# Ring_3_C.net
KiCad netlist of a schematic drawn in Altium Designer
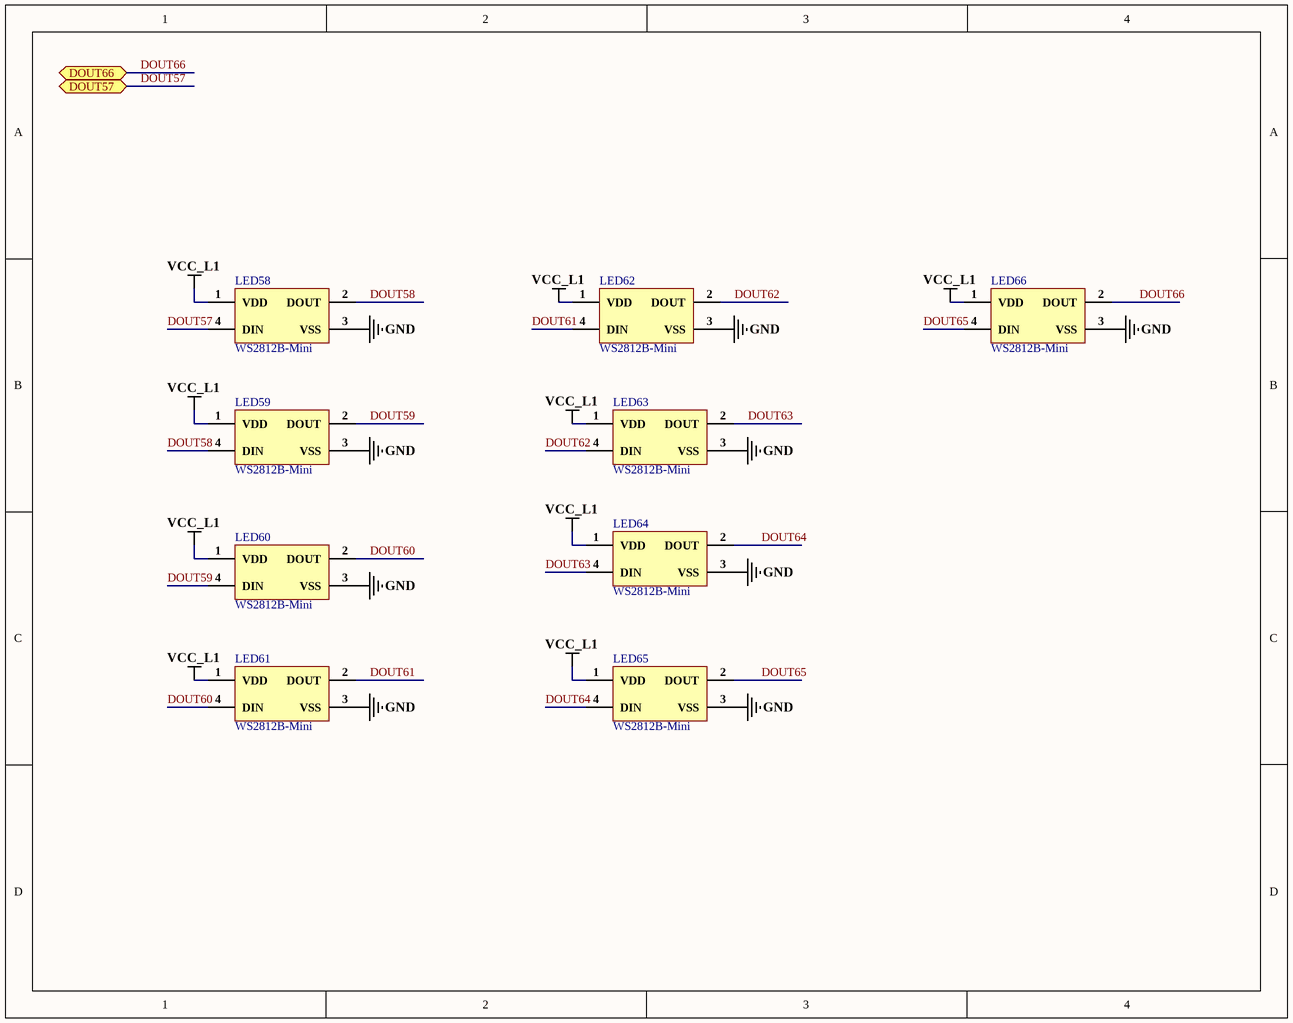
[diagram p0: Ring 3_C.SchDoc]

(export (version "E")
  (design (tool "Eeschema 10.0.6"))
  (components
    (comp (ref "LED58")
      (value "WS2812B-Mini")
      (footprint "WS2812B-Mini")
      (description "SMD,3.5x3.5mm Light Emitting Diodes (LED) RoHS")
      (fields (field (name "MANUFACTURER") "Worldsemi"))
      (libsource (lib "TT_IntLib") (part "WS2812B-Mini"))
    )
    (comp (ref "LED59")
      (value "WS2812B-Mini")
      (footprint "WS2812B-Mini")
      (description "SMD,3.5x3.5mm Light Emitting Diodes (LED) RoHS")
      (fields (field (name "MANUFACTURER") "Worldsemi"))
      (libsource (lib "TT_IntLib") (part "WS2812B-Mini"))
    )
    (comp (ref "LED60")
      (value "WS2812B-Mini")
      (footprint "WS2812B-Mini")
      (description "SMD,3.5x3.5mm Light Emitting Diodes (LED) RoHS")
      (fields (field (name "MANUFACTURER") "Worldsemi"))
      (libsource (lib "TT_IntLib") (part "WS2812B-Mini"))
    )
    (comp (ref "LED61")
      (value "WS2812B-Mini")
      (footprint "WS2812B-Mini")
      (description "SMD,3.5x3.5mm Light Emitting Diodes (LED) RoHS")
      (fields (field (name "MANUFACTURER") "Worldsemi"))
      (libsource (lib "TT_IntLib") (part "WS2812B-Mini"))
    )
    (comp (ref "LED62")
      (value "WS2812B-Mini")
      (footprint "WS2812B-Mini")
      (description "SMD,3.5x3.5mm Light Emitting Diodes (LED) RoHS")
      (fields (field (name "MANUFACTURER") "Worldsemi"))
      (libsource (lib "TT_IntLib") (part "WS2812B-Mini"))
    )
    (comp (ref "LED63")
      (value "WS2812B-Mini")
      (footprint "WS2812B-Mini")
      (description "SMD,3.5x3.5mm Light Emitting Diodes (LED) RoHS")
      (fields (field (name "MANUFACTURER") "Worldsemi"))
      (libsource (lib "TT_IntLib") (part "WS2812B-Mini"))
    )
    (comp (ref "LED64")
      (value "WS2812B-Mini")
      (footprint "WS2812B-Mini")
      (description "SMD,3.5x3.5mm Light Emitting Diodes (LED) RoHS")
      (fields (field (name "MANUFACTURER") "Worldsemi"))
      (libsource (lib "TT_IntLib") (part "WS2812B-Mini"))
    )
    (comp (ref "LED65")
      (value "WS2812B-Mini")
      (footprint "WS2812B-Mini")
      (description "SMD,3.5x3.5mm Light Emitting Diodes (LED) RoHS")
      (fields (field (name "MANUFACTURER") "Worldsemi"))
      (libsource (lib "TT_IntLib") (part "WS2812B-Mini"))
    )
    (comp (ref "LED66")
      (value "WS2812B-Mini")
      (footprint "WS2812B-Mini")
      (description "SMD,3.5x3.5mm Light Emitting Diodes (LED) RoHS")
      (fields (field (name "MANUFACTURER") "Worldsemi"))
      (libsource (lib "TT_IntLib") (part "WS2812B-Mini"))
    )
  )
  (nets
    (net (code "1") (name "/DOUT57") (class "Default")
      (node (ref "LED58") (pin "4") (pinfunction "DIN_4") (pintype "passive"))
    )
    (net (code "2") (name "/DOUT58") (class "Default")
      (node (ref "LED58") (pin "2") (pinfunction "DOUT_2") (pintype "passive"))
      (node (ref "LED59") (pin "4") (pinfunction "DIN_4") (pintype "passive"))
    )
    (net (code "3") (name "/DOUT59") (class "Default")
      (node (ref "LED59") (pin "2") (pinfunction "DOUT_2") (pintype "passive"))
      (node (ref "LED60") (pin "4") (pinfunction "DIN_4") (pintype "passive"))
    )
    (net (code "4") (name "/DOUT60") (class "Default")
      (node (ref "LED60") (pin "2") (pinfunction "DOUT_2") (pintype "passive"))
      (node (ref "LED61") (pin "4") (pinfunction "DIN_4") (pintype "passive"))
    )
    (net (code "5") (name "/DOUT61") (class "Default")
      (node (ref "LED61") (pin "2") (pinfunction "DOUT_2") (pintype "passive"))
      (node (ref "LED62") (pin "4") (pinfunction "DIN_4") (pintype "passive"))
    )
    (net (code "6") (name "/DOUT62") (class "Default")
      (node (ref "LED62") (pin "2") (pinfunction "DOUT_2") (pintype "passive"))
      (node (ref "LED63") (pin "4") (pinfunction "DIN_4") (pintype "passive"))
    )
    (net (code "7") (name "/DOUT63") (class "Default")
      (node (ref "LED63") (pin "2") (pinfunction "DOUT_2") (pintype "passive"))
      (node (ref "LED64") (pin "4") (pinfunction "DIN_4") (pintype "passive"))
    )
    (net (code "8") (name "/DOUT64") (class "Default")
      (node (ref "LED64") (pin "2") (pinfunction "DOUT_2") (pintype "passive"))
      (node (ref "LED65") (pin "4") (pinfunction "DIN_4") (pintype "passive"))
    )
    (net (code "9") (name "/DOUT65") (class "Default")
      (node (ref "LED65") (pin "2") (pinfunction "DOUT_2") (pintype "passive"))
      (node (ref "LED66") (pin "4") (pinfunction "DIN_4") (pintype "passive"))
    )
    (net (code "10") (name "/DOUT66") (class "Default")
      (node (ref "LED66") (pin "2") (pinfunction "DOUT_2") (pintype "passive"))
    )
    (net (code "11") (name "GND") (class "Default")
      (node (ref "LED58") (pin "3") (pinfunction "VSS_3") (pintype "passive"))
      (node (ref "LED59") (pin "3") (pinfunction "VSS_3") (pintype "passive"))
      (node (ref "LED60") (pin "3") (pinfunction "VSS_3") (pintype "passive"))
      (node (ref "LED61") (pin "3") (pinfunction "VSS_3") (pintype "passive"))
      (node (ref "LED62") (pin "3") (pinfunction "VSS_3") (pintype "passive"))
      (node (ref "LED63") (pin "3") (pinfunction "VSS_3") (pintype "passive"))
      (node (ref "LED64") (pin "3") (pinfunction "VSS_3") (pintype "passive"))
      (node (ref "LED65") (pin "3") (pinfunction "VSS_3") (pintype "passive"))
      (node (ref "LED66") (pin "3") (pinfunction "VSS_3") (pintype "passive"))
    )
    (net (code "12") (name "VCC_L1") (class "Default")
      (node (ref "LED58") (pin "1") (pinfunction "VDD_1") (pintype "passive"))
      (node (ref "LED59") (pin "1") (pinfunction "VDD_1") (pintype "passive"))
      (node (ref "LED60") (pin "1") (pinfunction "VDD_1") (pintype "passive"))
      (node (ref "LED61") (pin "1") (pinfunction "VDD_1") (pintype "passive"))
      (node (ref "LED62") (pin "1") (pinfunction "VDD_1") (pintype "passive"))
      (node (ref "LED63") (pin "1") (pinfunction "VDD_1") (pintype "passive"))
      (node (ref "LED64") (pin "1") (pinfunction "VDD_1") (pintype "passive"))
      (node (ref "LED65") (pin "1") (pinfunction "VDD_1") (pintype "passive"))
      (node (ref "LED66") (pin "1") (pinfunction "VDD_1") (pintype "passive"))
    )
  )
)
